# RFR24_AMS_Design_-_CAN_V1.net
KiCad netlist of a schematic drawn in Altium Designer
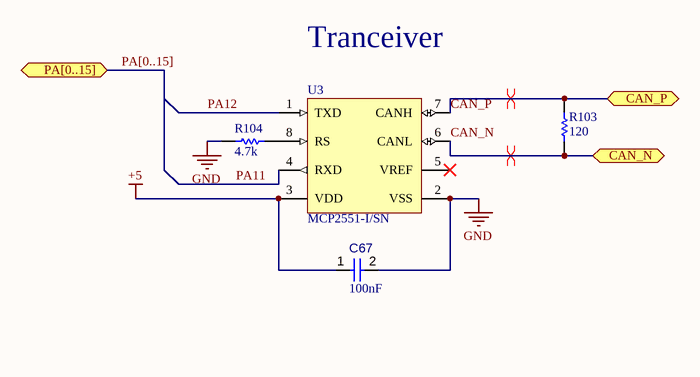
[diagram p0: RFR24 AMS Design - CAN V1.SchDoc]

(export (version "E")
  (design (tool "Eeschema 10.0.6"))
  (components
    (comp (ref "C67")
      (value "100nF")
      (footprint "CAPC2013X145X50LL20T25")
      (description "Chip Capacitor, 1 uF, +/-10%, 25 V, 0805 (2012 Metric)")
      (fields (field (name "TOLERANCE") "10%") (field (name "Comment") "Capacitor 1 uF +/- 10% 25 V 0805"))
      (libsource (lib "Rutgers University") (part "CAP-NP-2"))
    )
    (comp (ref "R103")
      (value "120")
      (footprint "RESC2013X70X40LL20T20")
      (description "Chip Resistor, 1 KOhm, +/- 1%, 0.125 W, -55 to 155 degC, 0805 (2013 Metric)")
      (fields (field (name "TOLERANCE") "1%") (field (name "POWER") "125mW"))
      (libsource (lib "Rutgers University") (part "RES-2"))
    )
    (comp (ref "R104")
      (value "4.7k")
      (footprint "RESC2013X70X40LL20T20")
      (description "Chip Resistor, 1 KOhm, +/- 1%, 0.125 W, -55 to 155 degC, 0805 (2013 Metric)")
      (fields (field (name "TOLERANCE") "1%") (field (name "POWER") "125mW"))
      (libsource (lib "Rutgers University") (part "RES-2"))
    )
    (comp (ref "U3")
      (value "MCP2551-I/SN")
      (footprint "MCHP-SN8_V")
      (fields (field (name "MANUFACTURER") "Microchip"))
      (libsource (lib "Altium Content Vault") (part "MCHP-MCP2551-SN8"))
    )
  )
  (nets
    (net (code "15") (name "+5") (class "Default")
      (node (ref "C67") (pin "1") (pinfunction "1_1") (pintype "passive"))
      (node (ref "U3") (pin "3") (pinfunction "VDD_3") (pintype "power_in"))
    )
    (net (code "16") (name "/CAN_N") (class "Default")
      (node (ref "R103") (pin "2") (pinfunction "2_2") (pintype "passive"))
      (node (ref "U3") (pin "6") (pinfunction "CANL_6") (pintype "bidirectional"))
    )
    (net (code "17") (name "/CAN_P") (class "Default")
      (node (ref "R103") (pin "1") (pinfunction "1_1") (pintype "passive"))
      (node (ref "U3") (pin "7") (pinfunction "CANH_7") (pintype "bidirectional"))
    )
    (net (code "18") (name "/PA11") (class "Default")
      (node (ref "U3") (pin "4") (pinfunction "RXD_4") (pintype "output"))
    )
    (net (code "19") (name "/PA12") (class "Default")
      (node (ref "U3") (pin "1") (pinfunction "TXD_1") (pintype "input"))
    )
    (net (code "21") (name "GND") (class "Default")
      (node (ref "C67") (pin "2") (pinfunction "2_2") (pintype "passive"))
      (node (ref "R104") (pin "1") (pinfunction "1_1") (pintype "passive"))
      (node (ref "U3") (pin "2") (pinfunction "VSS_2") (pintype "power_in"))
    )
    (net (code "22") (name "Net-(U3-RS)") (class "Default")
      (node (ref "R104") (pin "2") (pinfunction "2_2") (pintype "passive"))
      (node (ref "U3") (pin "8") (pinfunction "RS_8") (pintype "input"))
    )
    (net (code "23") (name "unconnected-(U3-VREF-Pad5)") (class "Default")
      (node (ref "U3") (pin "5") (pinfunction "VREF_5") (pintype "power_in+no_connect"))
    )
  )
)
